# Drum_robo.net
KiCad netlist of a schematic drawn in EAGLE
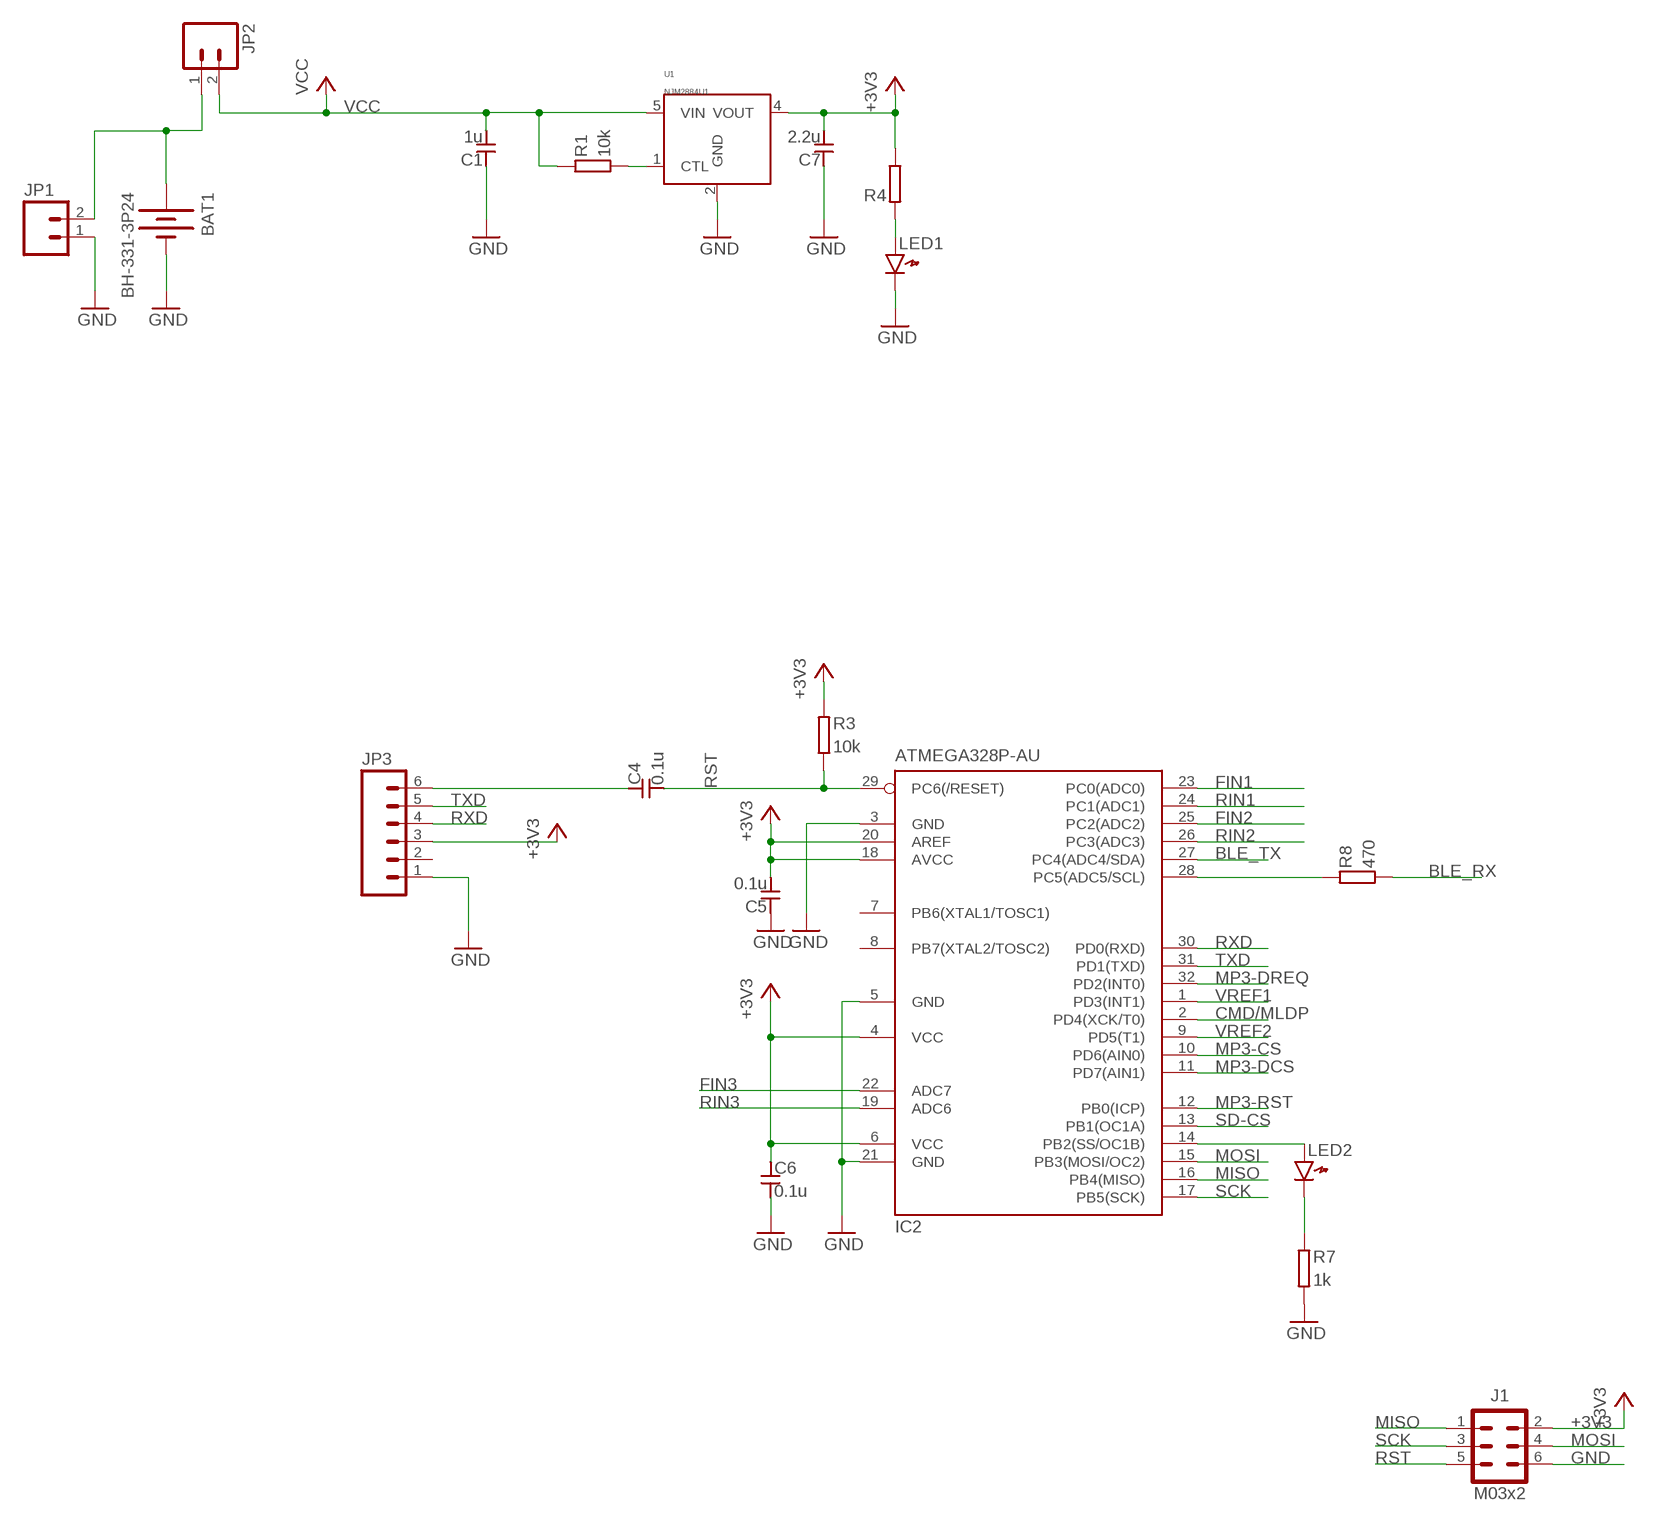
[diagram p0: schematic, sheet 1, part 1 of 2]
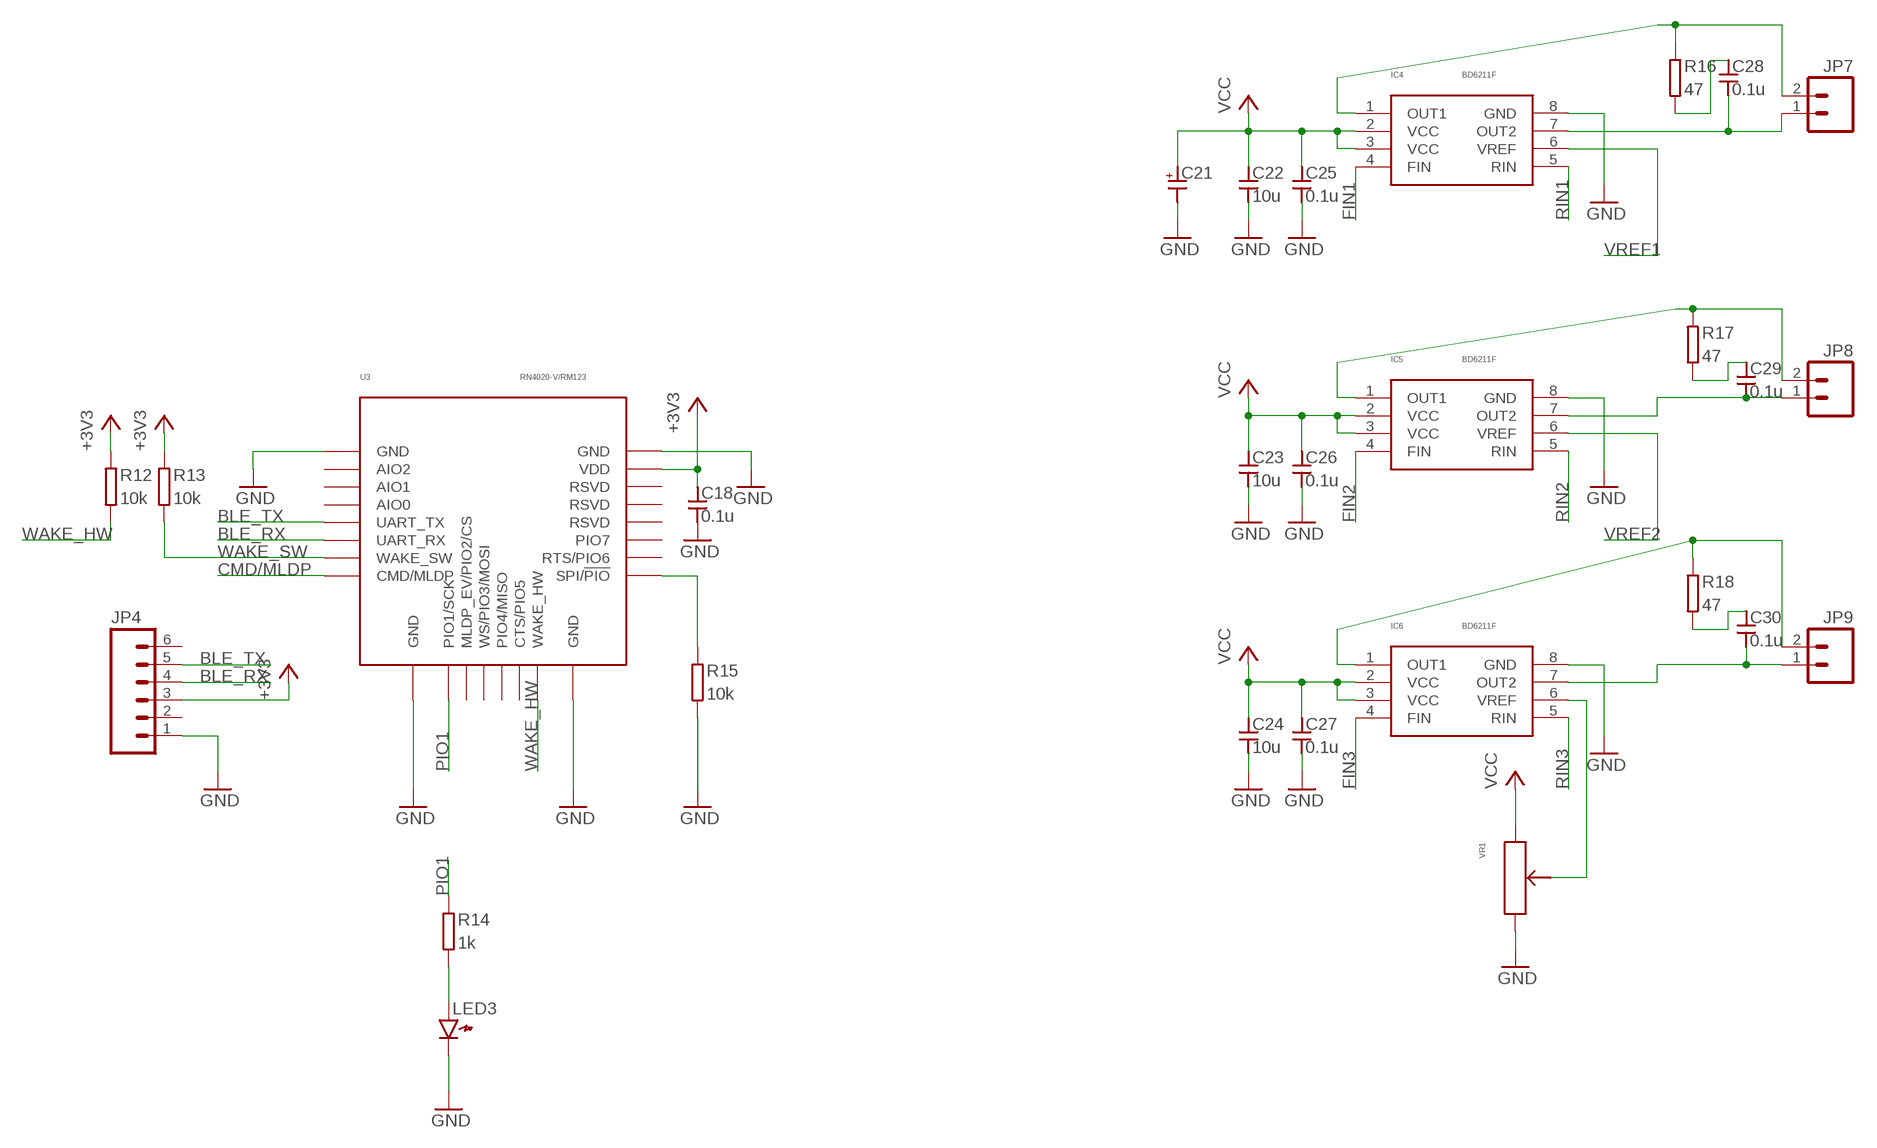
[diagram p1: schematic, sheet 1, part 2 of 2]

(export (version "E")
  (design (tool "Eeschema 10.0.6"))
  (components
    (comp (ref "BAT1")
      (value "BH-331-3P24")
      (footprint "eagle-import:BH-331-3P24")
      (libsource (lib "eagle-import") (part "BH-331-3P24"))
    )
    (comp (ref "C1")
      (value "1u")
      (footprint "eagle-import:SMD1608_REDUCED")
      (libsource (lib "eagle-import") (part "CAPACITOR1608_REDUCED"))
    )
    (comp (ref "C4")
      (value "0.1u")
      (footprint "eagle-import:SMD1608_REDUCED")
      (libsource (lib "eagle-import") (part "CAPACITOR1608_REDUCED"))
    )
    (comp (ref "C5")
      (value "0.1u")
      (footprint "eagle-import:SMD1608_REDUCED")
      (libsource (lib "eagle-import") (part "CAPACITOR1608_REDUCED"))
    )
    (comp (ref "C6")
      (value "0.1u")
      (footprint "eagle-import:SMD1608_REDUCED")
      (libsource (lib "eagle-import") (part "CAPACITOR1608_REDUCED"))
    )
    (comp (ref "C7")
      (value "2.2u")
      (footprint "eagle-import:SMD1608_REDUCED")
      (libsource (lib "eagle-import") (part "CAPACITOR1608_REDUCED"))
    )
    (comp (ref "C18")
      (value "0.1u")
      (footprint "eagle-import:SMD1608_REDUCED")
      (libsource (lib "eagle-import") (part "CAPACITOR1608_REDUCED"))
    )
    (comp (ref "C21")
      (value "CAPACITOR-POLPANASONIC_D")
      (footprint "eagle-import:PANASONIC_D")
      (libsource (lib "eagle-import") (part "CAPACITOR-POLPANASONIC_D"))
    )
    (comp (ref "C22")
      (value "10u")
      (footprint "eagle-import:SMD2012_REDUCED")
      (libsource (lib "eagle-import") (part "CAPACITOR2012_REDUCED"))
    )
    (comp (ref "C23")
      (value "10u")
      (footprint "eagle-import:SMD2012_REDUCED")
      (libsource (lib "eagle-import") (part "CAPACITOR2012_REDUCED"))
    )
    (comp (ref "C24")
      (value "10u")
      (footprint "eagle-import:SMD2012_REDUCED")
      (libsource (lib "eagle-import") (part "CAPACITOR2012_REDUCED"))
    )
    (comp (ref "C25")
      (value "0.1u")
      (footprint "eagle-import:SMD1608_REDUCED")
      (libsource (lib "eagle-import") (part "CAPACITOR1608_REDUCED"))
    )
    (comp (ref "C26")
      (value "0.1u")
      (footprint "eagle-import:SMD1608_REDUCED")
      (libsource (lib "eagle-import") (part "CAPACITOR1608_REDUCED"))
    )
    (comp (ref "C27")
      (value "0.1u")
      (footprint "eagle-import:SMD1608_REDUCED")
      (libsource (lib "eagle-import") (part "CAPACITOR1608_REDUCED"))
    )
    (comp (ref "C28")
      (value "0.1u")
      (footprint "eagle-import:SMD1608_REDUCED")
      (libsource (lib "eagle-import") (part "CAPACITOR1608_REDUCED"))
    )
    (comp (ref "C29")
      (value "0.1u")
      (footprint "eagle-import:SMD1608_REDUCED")
      (libsource (lib "eagle-import") (part "CAPACITOR1608_REDUCED"))
    )
    (comp (ref "C30")
      (value "0.1u")
      (footprint "eagle-import:SMD1608_REDUCED")
      (libsource (lib "eagle-import") (part "CAPACITOR1608_REDUCED"))
    )
    (comp (ref "IC2")
      (value "ATMEGA328P-AU")
      (footprint "eagle-import:TQFP32-08")
      (libsource (lib "eagle-import") (part "ATMEGA328P-AU"))
    )
    (comp (ref "IC4")
      (value "BD6211F")
      (footprint "eagle-import:SOP-8")
      (libsource (lib "eagle-import") (part "BD6211F"))
    )
    (comp (ref "IC5")
      (value "BD6211F")
      (footprint "eagle-import:SOP-8")
      (libsource (lib "eagle-import") (part "BD6211F"))
    )
    (comp (ref "IC6")
      (value "BD6211F")
      (footprint "eagle-import:SOP-8")
      (libsource (lib "eagle-import") (part "BD6211F"))
    )
    (comp (ref "J1")
      (value "M03X2STD")
      (footprint "eagle-import:2X03")
      (libsource (lib "eagle-import") (part "M03X2STD"))
    )
    (comp (ref "JP1")
      (value "M02NOSILK")
      (footprint "eagle-import:1X02-NOSILK")
      (libsource (lib "eagle-import") (part "M02NOSILK"))
    )
    (comp (ref "JP2")
      (value "M02NOSILK")
      (footprint "eagle-import:1X02-NOSILK")
      (libsource (lib "eagle-import") (part "M02NOSILK"))
    )
    (comp (ref "JP3")
      (value "M06NOSILK")
      (footprint "eagle-import:1X06-NOSILK")
      (libsource (lib "eagle-import") (part "M06NOSILK"))
    )
    (comp (ref "JP4")
      (value "M06NOSILK")
      (footprint "eagle-import:1X06-NOSILK")
      (libsource (lib "eagle-import") (part "M06NOSILK"))
    )
    (comp (ref "JP7")
      (value "M02NOSILK")
      (footprint "eagle-import:1X02-NOSILK")
      (libsource (lib "eagle-import") (part "M02NOSILK"))
    )
    (comp (ref "JP8")
      (value "M02NOSILK")
      (footprint "eagle-import:1X02-NOSILK")
      (libsource (lib "eagle-import") (part "M02NOSILK"))
    )
    (comp (ref "JP9")
      (value "M02NOSILK")
      (footprint "eagle-import:1X02-NOSILK")
      (libsource (lib "eagle-import") (part "M02NOSILK"))
    )
    (comp (ref "LED1")
      (value "LED1608_REDUCED")
      (footprint "eagle-import:LED1608_REDUCED")
      (libsource (lib "eagle-import") (part "LED1608_REDUCED"))
    )
    (comp (ref "LED2")
      (value "LED1608_REDUCED")
      (footprint "eagle-import:LED1608_REDUCED")
      (libsource (lib "eagle-import") (part "LED1608_REDUCED"))
    )
    (comp (ref "LED3")
      (value "LED1608_REDUCED")
      (footprint "eagle-import:LED1608_REDUCED")
      (libsource (lib "eagle-import") (part "LED1608_REDUCED"))
    )
    (comp (ref "R1")
      (value "10k")
      (footprint "eagle-import:SMD1608_REDUCED")
      (libsource (lib "eagle-import") (part "RESISTOR1608_REDUCED"))
    )
    (comp (ref "R3")
      (value "10k")
      (footprint "eagle-import:SMD1608_REDUCED")
      (libsource (lib "eagle-import") (part "RESISTOR1608_REDUCED"))
    )
    (comp (ref "R4")
      (value "RESISTOR1608_REDUCED")
      (footprint "eagle-import:SMD1608_REDUCED")
      (libsource (lib "eagle-import") (part "RESISTOR1608_REDUCED"))
    )
    (comp (ref "R7")
      (value "1k")
      (footprint "eagle-import:SMD1608_REDUCED")
      (libsource (lib "eagle-import") (part "RESISTOR1608_REDUCED"))
    )
    (comp (ref "R8")
      (value "470")
      (footprint "eagle-import:SMD1608_REDUCED")
      (libsource (lib "eagle-import") (part "RESISTOR1608_REDUCED"))
    )
    (comp (ref "R12")
      (value "10k")
      (footprint "eagle-import:SMD1608_REDUCED")
      (libsource (lib "eagle-import") (part "RESISTOR1608_REDUCED"))
    )
    (comp (ref "R13")
      (value "10k")
      (footprint "eagle-import:SMD1608_REDUCED")
      (libsource (lib "eagle-import") (part "RESISTOR1608_REDUCED"))
    )
    (comp (ref "R14")
      (value "1k")
      (footprint "eagle-import:SMD1608_REDUCED")
      (libsource (lib "eagle-import") (part "RESISTOR1608_REDUCED"))
    )
    (comp (ref "R15")
      (value "10k")
      (footprint "eagle-import:SMD1608_REDUCED")
      (libsource (lib "eagle-import") (part "RESISTOR1608_REDUCED"))
    )
    (comp (ref "R16")
      (value "47")
      (footprint "eagle-import:SMD1608_REDUCED")
      (libsource (lib "eagle-import") (part "RESISTOR1608_REDUCED"))
    )
    (comp (ref "R17")
      (value "47")
      (footprint "eagle-import:SMD1608_REDUCED")
      (libsource (lib "eagle-import") (part "RESISTOR1608_REDUCED"))
    )
    (comp (ref "R18")
      (value "47")
      (footprint "eagle-import:SMD1608_REDUCED")
      (libsource (lib "eagle-import") (part "RESISTOR1608_REDUCED"))
    )
    (comp (ref "U1")
      (value "NJM2884U1")
      (footprint "eagle-import:SOT-89-5")
      (libsource (lib "eagle-import") (part "NJM2884U1"))
    )
    (comp (ref "U3")
      (value "RN4020-V/RM123")
      (footprint "eagle-import:RN4020")
      (libsource (lib "eagle-import") (part "RN4020-V/RM123"))
    )
    (comp (ref "VR1")
      (value "VR")
      (footprint "eagle-import:3362P")
      (libsource (lib "eagle-import") (part "VR"))
    )
  )
  (nets
    (net (code "1") (name "+3V3") (class "Default")
      (node (ref "C18") (pin "1") (pinfunction "1_1") (pintype "passive"))
      (node (ref "C5") (pin "2") (pinfunction "2_2") (pintype "passive"))
      (node (ref "C6") (pin "1") (pinfunction "1_1") (pintype "passive"))
      (node (ref "C7") (pin "2") (pinfunction "2_2") (pintype "passive"))
      (node (ref "IC2") (pin "18") (pinfunction "AVCC_18") (pintype "power_in"))
      (node (ref "IC2") (pin "20") (pinfunction "AREF_20") (pintype "passive"))
      (node (ref "IC2") (pin "4") (pinfunction "VCC_4") (pintype "power_in"))
      (node (ref "IC2") (pin "6") (pinfunction "VCC_6") (pintype "power_in"))
      (node (ref "J1") (pin "2") (pinfunction "2_2") (pintype "bidirectional"))
      (node (ref "JP3") (pin "3") (pinfunction "3_3") (pintype "passive"))
      (node (ref "JP4") (pin "3") (pinfunction "3_3") (pintype "passive"))
      (node (ref "R12") (pin "1") (pinfunction "1_1") (pintype "passive"))
      (node (ref "R13") (pin "1") (pinfunction "1_1") (pintype "passive"))
      (node (ref "R3") (pin "1") (pinfunction "1_1") (pintype "passive"))
      (node (ref "R4") (pin "2") (pinfunction "2_2") (pintype "passive"))
      (node (ref "U1") (pin "4") (pinfunction "VOUT_4") (pintype "bidirectional"))
      (node (ref "U3") (pin "23") (pinfunction "VDD_23") (pintype "bidirectional"))
    )
    (net (code "2") (name "/BLE_RX") (class "Default")
      (node (ref "JP4") (pin "4") (pinfunction "4_4") (pintype "passive"))
      (node (ref "R8") (pin "2") (pinfunction "2_2") (pintype "passive"))
      (node (ref "U3") (pin "6") (pinfunction "UART_RX_6") (pintype "bidirectional"))
    )
    (net (code "3") (name "/BLE_TX") (class "Default")
      (node (ref "IC2") (pin "27") (pinfunction "PC4(ADC4/SDA)_27") (pintype "bidirectional"))
      (node (ref "JP4") (pin "5") (pinfunction "5_5") (pintype "passive"))
      (node (ref "U3") (pin "5") (pinfunction "UART_TX_5") (pintype "bidirectional"))
    )
    (net (code "4") (name "/CMD{slash}MLDP") (class "Default")
      (node (ref "IC2") (pin "2") (pinfunction "PD4(XCK/T0)_2") (pintype "bidirectional"))
      (node (ref "U3") (pin "8") (pinfunction "CMD/MLDP_8") (pintype "bidirectional"))
    )
    (net (code "5") (name "/FIN1") (class "Default")
      (node (ref "IC2") (pin "23") (pinfunction "PC0(ADC0)_23") (pintype "bidirectional"))
      (node (ref "IC4") (pin "4") (pinfunction "FIN_4") (pintype "bidirectional"))
    )
    (net (code "6") (name "/FIN2") (class "Default")
      (node (ref "IC2") (pin "25") (pinfunction "PC2(ADC2)_25") (pintype "bidirectional"))
      (node (ref "IC5") (pin "4") (pinfunction "FIN_4") (pintype "bidirectional"))
    )
    (net (code "7") (name "/FIN3") (class "Default")
      (node (ref "IC2") (pin "22") (pinfunction "ADC7_22") (pintype "input"))
      (node (ref "IC6") (pin "4") (pinfunction "FIN_4") (pintype "bidirectional"))
    )
    (net (code "8") (name "/MISO") (class "Default")
      (node (ref "IC2") (pin "16") (pinfunction "PB4(MISO)_16") (pintype "bidirectional"))
      (node (ref "J1") (pin "1") (pinfunction "1_1") (pintype "bidirectional"))
    )
    (net (code "9") (name "/MOSI") (class "Default")
      (node (ref "IC2") (pin "15") (pinfunction "PB3(MOSI/OC2)_15") (pintype "bidirectional"))
      (node (ref "J1") (pin "4") (pinfunction "4_4") (pintype "bidirectional"))
    )
    (net (code "10") (name "/MP3-CS") (class "Default")
      (node (ref "IC2") (pin "10") (pinfunction "PD6(AIN0)_10") (pintype "bidirectional"))
    )
    (net (code "11") (name "/MP3-DCS") (class "Default")
      (node (ref "IC2") (pin "11") (pinfunction "PD7(AIN1)_11") (pintype "bidirectional"))
    )
    (net (code "12") (name "/MP3-DREQ") (class "Default")
      (node (ref "IC2") (pin "32") (pinfunction "PD2(INT0)_32") (pintype "bidirectional"))
    )
    (net (code "13") (name "/MP3-RST") (class "Default")
      (node (ref "IC2") (pin "12") (pinfunction "PB0(ICP)_12") (pintype "bidirectional"))
    )
    (net (code "14") (name "/PIO1") (class "Default")
      (node (ref "R14") (pin "1") (pinfunction "1_1") (pintype "passive"))
      (node (ref "U3") (pin "10") (pinfunction "PIO1/SCK_10") (pintype "bidirectional"))
    )
    (net (code "15") (name "/RIN1") (class "Default")
      (node (ref "IC2") (pin "24") (pinfunction "PC1(ADC1)_24") (pintype "bidirectional"))
      (node (ref "IC4") (pin "5") (pinfunction "RIN_5") (pintype "bidirectional"))
    )
    (net (code "16") (name "/RIN2") (class "Default")
      (node (ref "IC2") (pin "26") (pinfunction "PC3(ADC3)_26") (pintype "bidirectional"))
      (node (ref "IC5") (pin "5") (pinfunction "RIN_5") (pintype "bidirectional"))
    )
    (net (code "17") (name "/RIN3") (class "Default")
      (node (ref "IC2") (pin "19") (pinfunction "ADC6_19") (pintype "input"))
      (node (ref "IC6") (pin "5") (pinfunction "RIN_5") (pintype "bidirectional"))
    )
    (net (code "18") (name "/RST") (class "Default")
      (node (ref "C4") (pin "2") (pinfunction "2_2") (pintype "passive"))
      (node (ref "IC2") (pin "29") (pinfunction "PC6(/RESET)_29") (pintype "bidirectional"))
      (node (ref "J1") (pin "5") (pinfunction "5_5") (pintype "bidirectional"))
      (node (ref "R3") (pin "2") (pinfunction "2_2") (pintype "passive"))
    )
    (net (code "19") (name "/RXD") (class "Default")
      (node (ref "IC2") (pin "30") (pinfunction "PD0(RXD)_30") (pintype "bidirectional"))
      (node (ref "JP3") (pin "4") (pinfunction "4_4") (pintype "passive"))
    )
    (net (code "20") (name "/SCK") (class "Default")
      (node (ref "IC2") (pin "17") (pinfunction "PB5(SCK)_17") (pintype "bidirectional"))
      (node (ref "J1") (pin "3") (pinfunction "3_3") (pintype "bidirectional"))
    )
    (net (code "21") (name "/SD-CS") (class "Default")
      (node (ref "IC2") (pin "13") (pinfunction "PB1(OC1A)_13") (pintype "bidirectional"))
    )
    (net (code "22") (name "/TXD") (class "Default")
      (node (ref "IC2") (pin "31") (pinfunction "PD1(TXD)_31") (pintype "bidirectional"))
      (node (ref "JP3") (pin "5") (pinfunction "5_5") (pintype "passive"))
    )
    (net (code "23") (name "/VREF1") (class "Default")
      (node (ref "IC2") (pin "1") (pinfunction "PD3(INT1)_1") (pintype "bidirectional"))
      (node (ref "IC4") (pin "6") (pinfunction "VREF_6") (pintype "bidirectional"))
    )
    (net (code "24") (name "/VREF2") (class "Default")
      (node (ref "IC2") (pin "9") (pinfunction "PD5(T1)_9") (pintype "bidirectional"))
      (node (ref "IC5") (pin "6") (pinfunction "VREF_6") (pintype "bidirectional"))
    )
    (net (code "25") (name "/WAKE_HW") (class "Default")
      (node (ref "R12") (pin "2") (pinfunction "2_2") (pintype "passive"))
      (node (ref "U3") (pin "15") (pinfunction "WAKE_HW_15") (pintype "bidirectional"))
    )
    (net (code "26") (name "/WAKE_SW") (class "Default")
      (node (ref "R13") (pin "2") (pinfunction "2_2") (pintype "passive"))
      (node (ref "U3") (pin "7") (pinfunction "WAKE_SW_7") (pintype "bidirectional"))
    )
    (net (code "27") (name "GND") (class "Default")
      (node (ref "BAT1") (pin "-") (pinfunction "-_-") (pintype "power_in"))
      (node (ref "C1") (pin "1") (pinfunction "1_1") (pintype "passive"))
      (node (ref "C18") (pin "2") (pinfunction "2_2") (pintype "passive"))
      (node (ref "C21") (pin "-") (pinfunction "-_-") (pintype "passive"))
      (node (ref "C22") (pin "2") (pinfunction "2_2") (pintype "passive"))
      (node (ref "C23") (pin "2") (pinfunction "2_2") (pintype "passive"))
      (node (ref "C24") (pin "2") (pinfunction "2_2") (pintype "passive"))
      (node (ref "C25") (pin "2") (pinfunction "2_2") (pintype "passive"))
      (node (ref "C26") (pin "2") (pinfunction "2_2") (pintype "passive"))
      (node (ref "C27") (pin "2") (pinfunction "2_2") (pintype "passive"))
      (node (ref "C5") (pin "1") (pinfunction "1_1") (pintype "passive"))
      (node (ref "C6") (pin "2") (pinfunction "2_2") (pintype "passive"))
      (node (ref "C7") (pin "1") (pinfunction "1_1") (pintype "passive"))
      (node (ref "IC2") (pin "21") (pinfunction "GND_21") (pintype "power_in"))
      (node (ref "IC2") (pin "3") (pinfunction "GND_3") (pintype "power_in"))
      (node (ref "IC2") (pin "5") (pinfunction "GND_5") (pintype "power_in"))
      (node (ref "IC4") (pin "8") (pinfunction "GND_8") (pintype "bidirectional"))
      (node (ref "IC5") (pin "8") (pinfunction "GND_8") (pintype "bidirectional"))
      (node (ref "IC6") (pin "8") (pinfunction "GND_8") (pintype "bidirectional"))
      (node (ref "J1") (pin "6") (pinfunction "6_6") (pintype "bidirectional"))
      (node (ref "JP1") (pin "1") (pinfunction "1_1") (pintype "passive"))
      (node (ref "JP3") (pin "1") (pinfunction "1_1") (pintype "passive"))
      (node (ref "JP4") (pin "1") (pinfunction "1_1") (pintype "passive"))
      (node (ref "LED1") (pin "K") (pinfunction "K_K") (pintype "passive"))
      (node (ref "LED3") (pin "K") (pinfunction "K_K") (pintype "passive"))
      (node (ref "R15") (pin "2") (pinfunction "2_2") (pintype "passive"))
      (node (ref "R7") (pin "2") (pinfunction "2_2") (pintype "passive"))
      (node (ref "U1") (pin "2") (pinfunction "GND_2") (pintype "bidirectional"))
      (node (ref "U3") (pin "1") (pinfunction "GND_1") (pintype "bidirectional"))
      (node (ref "U3") (pin "16") (pinfunction "GND_16") (pintype "bidirectional"))
      (node (ref "U3") (pin "24") (pinfunction "GND_24") (pintype "bidirectional"))
      (node (ref "U3") (pin "9") (pinfunction "GND_9") (pintype "bidirectional"))
      (node (ref "VR1") (pin "3") (pinfunction "3_3") (pintype "bidirectional"))
    )
    (net (code "28") (name "Net-(BAT1-Pad+)") (class "Default")
      (node (ref "BAT1") (pin "+") (pinfunction "+_+") (pintype "power_in"))
      (node (ref "JP1") (pin "2") (pinfunction "2_2") (pintype "passive"))
      (node (ref "JP2") (pin "1") (pinfunction "1_1") (pintype "passive"))
    )
    (net (code "29") (name "Net-(C4-Pad1)") (class "Default")
      (node (ref "C4") (pin "1") (pinfunction "1_1") (pintype "passive"))
      (node (ref "JP3") (pin "6") (pinfunction "6_6") (pintype "passive"))
    )
    (net (code "30") (name "Net-(C28-Pad1)") (class "Default")
      (node (ref "C28") (pin "1") (pinfunction "1_1") (pintype "passive"))
      (node (ref "R16") (pin "2") (pinfunction "2_2") (pintype "passive"))
    )
    (net (code "31") (name "Net-(C29-Pad1)") (class "Default")
      (node (ref "C29") (pin "1") (pinfunction "1_1") (pintype "passive"))
      (node (ref "R17") (pin "2") (pinfunction "2_2") (pintype "passive"))
    )
    (net (code "32") (name "Net-(C30-Pad1)") (class "Default")
      (node (ref "C30") (pin "1") (pinfunction "1_1") (pintype "passive"))
      (node (ref "R18") (pin "2") (pinfunction "2_2") (pintype "passive"))
    )
    (net (code "33") (name "Net-(IC2-PB2(SS{slash}OC1B))") (class "Default")
      (node (ref "IC2") (pin "14") (pinfunction "PB2(SS/OC1B)_14") (pintype "bidirectional"))
      (node (ref "LED2") (pin "A") (pinfunction "A_A") (pintype "passive"))
    )
    (net (code "34") (name "Net-(IC2-PC5(ADC5{slash}SCL))") (class "Default")
      (node (ref "IC2") (pin "28") (pinfunction "PC5(ADC5/SCL)_28") (pintype "bidirectional"))
      (node (ref "R8") (pin "1") (pinfunction "1_1") (pintype "passive"))
    )
    (net (code "35") (name "Net-(IC4-OUT1)") (class "Default")
      (node (ref "IC4") (pin "1") (pinfunction "OUT1_1") (pintype "bidirectional"))
      (node (ref "JP7") (pin "2") (pinfunction "2_2") (pintype "passive"))
      (node (ref "R16") (pin "1") (pinfunction "1_1") (pintype "passive"))
    )
    (net (code "36") (name "Net-(IC4-OUT2)") (class "Default")
      (node (ref "C28") (pin "2") (pinfunction "2_2") (pintype "passive"))
      (node (ref "IC4") (pin "7") (pinfunction "OUT2_7") (pintype "bidirectional"))
      (node (ref "JP7") (pin "1") (pinfunction "1_1") (pintype "passive"))
    )
    (net (code "37") (name "Net-(IC5-OUT1)") (class "Default")
      (node (ref "IC5") (pin "1") (pinfunction "OUT1_1") (pintype "bidirectional"))
      (node (ref "JP8") (pin "2") (pinfunction "2_2") (pintype "passive"))
      (node (ref "R17") (pin "1") (pinfunction "1_1") (pintype "passive"))
    )
    (net (code "38") (name "Net-(IC5-OUT2)") (class "Default")
      (node (ref "C29") (pin "2") (pinfunction "2_2") (pintype "passive"))
      (node (ref "IC5") (pin "7") (pinfunction "OUT2_7") (pintype "bidirectional"))
      (node (ref "JP8") (pin "1") (pinfunction "1_1") (pintype "passive"))
    )
    (net (code "39") (name "Net-(IC6-OUT1)") (class "Default")
      (node (ref "IC6") (pin "1") (pinfunction "OUT1_1") (pintype "bidirectional"))
      (node (ref "JP9") (pin "2") (pinfunction "2_2") (pintype "passive"))
      (node (ref "R18") (pin "1") (pinfunction "1_1") (pintype "passive"))
    )
    (net (code "40") (name "Net-(IC6-OUT2)") (class "Default")
      (node (ref "C30") (pin "2") (pinfunction "2_2") (pintype "passive"))
      (node (ref "IC6") (pin "7") (pinfunction "OUT2_7") (pintype "bidirectional"))
      (node (ref "JP9") (pin "1") (pinfunction "1_1") (pintype "passive"))
    )
    (net (code "41") (name "Net-(IC6-VREF)") (class "Default")
      (node (ref "IC6") (pin "6") (pinfunction "VREF_6") (pintype "bidirectional"))
      (node (ref "VR1") (pin "2") (pinfunction "2_2") (pintype "bidirectional"))
    )
    (net (code "42") (name "Net-(LED1-PadA)") (class "Default")
      (node (ref "LED1") (pin "A") (pinfunction "A_A") (pintype "passive"))
      (node (ref "R4") (pin "1") (pinfunction "1_1") (pintype "passive"))
    )
    (net (code "43") (name "Net-(LED2-PadK)") (class "Default")
      (node (ref "LED2") (pin "K") (pinfunction "K_K") (pintype "passive"))
      (node (ref "R7") (pin "1") (pinfunction "1_1") (pintype "passive"))
    )
    (net (code "44") (name "Net-(LED3-PadA)") (class "Default")
      (node (ref "LED3") (pin "A") (pinfunction "A_A") (pintype "passive"))
      (node (ref "R14") (pin "2") (pinfunction "2_2") (pintype "passive"))
    )
    (net (code "45") (name "Net-(U1-CTL)") (class "Default")
      (node (ref "R1") (pin "2") (pinfunction "2_2") (pintype "passive"))
      (node (ref "U1") (pin "1") (pinfunction "CTL_1") (pintype "bidirectional"))
    )
    (net (code "46") (name "Net-(U3-SPI{slash}~{PIO})") (class "Default")
      (node (ref "R15") (pin "1") (pinfunction "1_1") (pintype "passive"))
      (node (ref "U3") (pin "17") (pinfunction "SPI/~{PIO}_17") (pintype "bidirectional"))
    )
    (net (code "47") (name "VCC") (class "Default")
      (node (ref "C1") (pin "2") (pinfunction "2_2") (pintype "passive"))
      (node (ref "C21") (pin "+") (pinfunction "+_+") (pintype "passive"))
      (node (ref "C22") (pin "1") (pinfunction "1_1") (pintype "passive"))
      (node (ref "C23") (pin "1") (pinfunction "1_1") (pintype "passive"))
      (node (ref "C24") (pin "1") (pinfunction "1_1") (pintype "passive"))
      (node (ref "C25") (pin "1") (pinfunction "1_1") (pintype "passive"))
      (node (ref "C26") (pin "1") (pinfunction "1_1") (pintype "passive"))
      (node (ref "C27") (pin "1") (pinfunction "1_1") (pintype "passive"))
      (node (ref "IC4") (pin "2") (pinfunction "VCC_2") (pintype "bidirectional"))
      (node (ref "IC4") (pin "3") (pinfunction "VCC_3") (pintype "bidirectional"))
      (node (ref "IC5") (pin "2") (pinfunction "VCC_2") (pintype "bidirectional"))
      (node (ref "IC5") (pin "3") (pinfunction "VCC_3") (pintype "bidirectional"))
      (node (ref "IC6") (pin "2") (pinfunction "VCC_2") (pintype "bidirectional"))
      (node (ref "IC6") (pin "3") (pinfunction "VCC_3") (pintype "bidirectional"))
      (node (ref "JP2") (pin "2") (pinfunction "2_2") (pintype "passive"))
      (node (ref "R1") (pin "1") (pinfunction "1_1") (pintype "passive"))
      (node (ref "U1") (pin "5") (pinfunction "VIN_5") (pintype "bidirectional"))
      (node (ref "VR1") (pin "1") (pinfunction "1_1") (pintype "bidirectional"))
    )
    (net (code "48") (name "unconnected-(IC2-PB6(XTAL1{slash}TOSC1)-Pad7)") (class "Default")
      (node (ref "IC2") (pin "7") (pinfunction "PB6(XTAL1/TOSC1)_7") (pintype "bidirectional"))
    )
    (net (code "49") (name "unconnected-(IC2-PB7(XTAL2{slash}TOSC2)-Pad8)") (class "Default")
      (node (ref "IC2") (pin "8") (pinfunction "PB7(XTAL2/TOSC2)_8") (pintype "bidirectional"))
    )
    (net (code "50") (name "unconnected-(JP3-Pad2)") (class "Default")
      (node (ref "JP3") (pin "2") (pinfunction "2_2") (pintype "passive"))
    )
    (net (code "51") (name "unconnected-(JP4-Pad2)") (class "Default")
      (node (ref "JP4") (pin "2") (pinfunction "2_2") (pintype "passive"))
    )
    (net (code "52") (name "unconnected-(JP4-Pad6)") (class "Default")
      (node (ref "JP4") (pin "6") (pinfunction "6_6") (pintype "passive"))
    )
    (net (code "53") (name "unconnected-(U3-AIO0-Pad4)") (class "Default")
      (node (ref "U3") (pin "4") (pinfunction "AIO0_4") (pintype "bidirectional"))
    )
    (net (code "54") (name "unconnected-(U3-AIO1-Pad3)") (class "Default")
      (node (ref "U3") (pin "3") (pinfunction "AIO1_3") (pintype "bidirectional"))
    )
    (net (code "55") (name "unconnected-(U3-AIO2-Pad2)") (class "Default")
      (node (ref "U3") (pin "2") (pinfunction "AIO2_2") (pintype "bidirectional"))
    )
    (net (code "56") (name "unconnected-(U3-CTS{slash}PIO5-Pad14)") (class "Default")
      (node (ref "U3") (pin "14") (pinfunction "CTS/PIO5_14") (pintype "bidirectional"))
    )
    (net (code "57") (name "unconnected-(U3-MLDP_EV{slash}PIO2{slash}CS-Pad11)") (class "Default")
      (node (ref "U3") (pin "11") (pinfunction "MLDP_EV/PIO2/CS_11") (pintype "bidirectional"))
    )
    (net (code "58") (name "unconnected-(U3-PIO4{slash}MISO-Pad13)") (class "Default")
      (node (ref "U3") (pin "13") (pinfunction "PIO4/MISO_13") (pintype "bidirectional"))
    )
    (net (code "59") (name "unconnected-(U3-PIO7-Pad19)") (class "Default")
      (node (ref "U3") (pin "19") (pinfunction "PIO7_19") (pintype "bidirectional"))
    )
    (net (code "60") (name "unconnected-(U3-RSVD-Pad20)") (class "Default")
      (node (ref "U3") (pin "20") (pinfunction "RSVD_20") (pintype "bidirectional"))
    )
    (net (code "61") (name "unconnected-(U3-RSVD-Pad21)") (class "Default")
      (node (ref "U3") (pin "21") (pinfunction "RSVD_21") (pintype "bidirectional"))
    )
    (net (code "62") (name "unconnected-(U3-RSVD-Pad22)") (class "Default")
      (node (ref "U3") (pin "22") (pinfunction "RSVD_22") (pintype "bidirectional"))
    )
    (net (code "63") (name "unconnected-(U3-RTS{slash}PIO6-Pad18)") (class "Default")
      (node (ref "U3") (pin "18") (pinfunction "RTS/PIO6_18") (pintype "bidirectional"))
    )
    (net (code "64") (name "unconnected-(U3-WS{slash}PIO3{slash}MOSI-Pad12)") (class "Default")
      (node (ref "U3") (pin "12") (pinfunction "WS/PIO3/MOSI_12") (pintype "bidirectional"))
    )
  )
)
